# capsens.net
KiCad netlist of a schematic drawn in Altium Designer
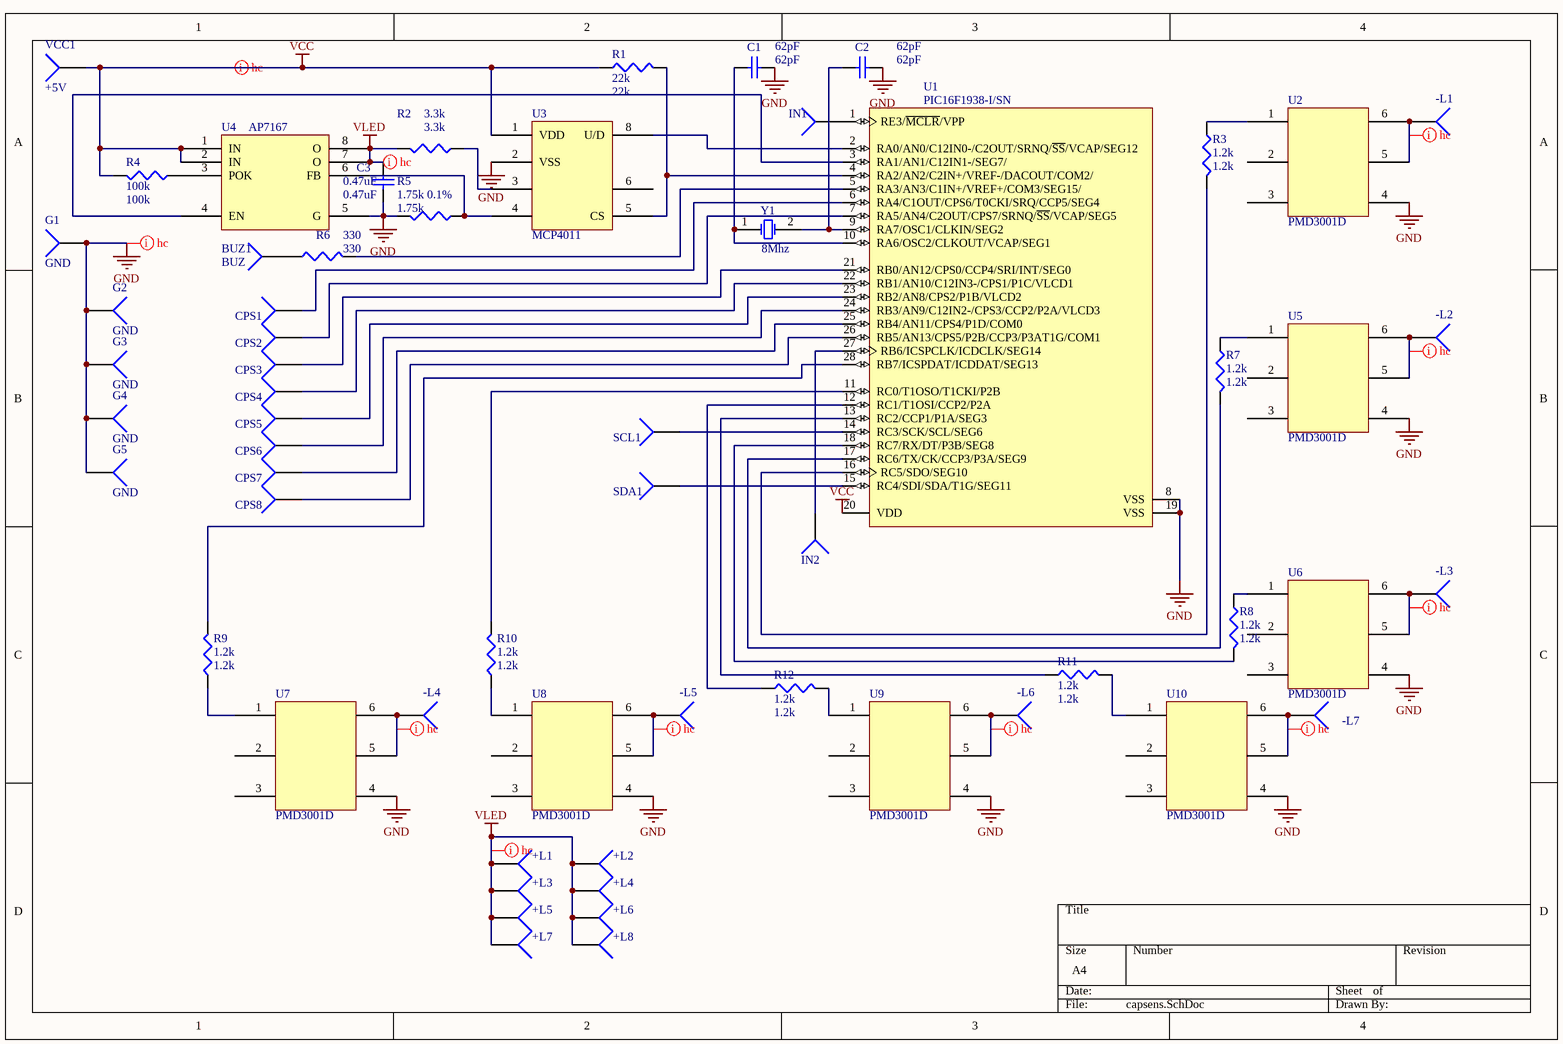
[diagram p0: capsens.SchDoc]

(export (version "E")
  (design (tool "Eeschema 10.0.6"))
  (components
    (comp (ref "+L1")
      (value "+L")
      (footprint "PIN1")
      (description "Socket")
      (fields (field (name "PUBLISHER") "Altium Limited"))
      (libsource (lib "misc") (part "Socket"))
    )
    (comp (ref "+L2")
      (value "+L")
      (footprint "PIN1")
      (description "Socket")
      (fields (field (name "PUBLISHER") "Altium Limited"))
      (libsource (lib "misc") (part "Socket"))
    )
    (comp (ref "+L3")
      (value "+L")
      (footprint "PIN1")
      (description "Socket")
      (fields (field (name "PUBLISHER") "Altium Limited"))
      (libsource (lib "misc") (part "Socket"))
    )
    (comp (ref "+L4")
      (value "+L")
      (footprint "PIN1")
      (description "Socket")
      (fields (field (name "PUBLISHER") "Altium Limited"))
      (libsource (lib "misc") (part "Socket"))
    )
    (comp (ref "+L5")
      (value "+L")
      (footprint "PIN1")
      (description "Socket")
      (fields (field (name "PUBLISHER") "Altium Limited"))
      (libsource (lib "misc") (part "Socket"))
    )
    (comp (ref "+L6")
      (value "+L")
      (footprint "PIN1")
      (description "Socket")
      (fields (field (name "PUBLISHER") "Altium Limited"))
      (libsource (lib "misc") (part "Socket"))
    )
    (comp (ref "+L7")
      (value "+L")
      (footprint "PIN1")
      (description "Socket")
      (fields (field (name "PUBLISHER") "Altium Limited"))
      (libsource (lib "misc") (part "Socket"))
    )
    (comp (ref "+L8")
      (value "+L")
      (footprint "PIN1")
      (description "Socket")
      (fields (field (name "PUBLISHER") "Altium Limited"))
      (libsource (lib "misc") (part "Socket"))
    )
    (comp (ref "-L1")
      (value "-L")
      (footprint "PIN1")
      (description "Socket")
      (fields (field (name "PUBLISHER") "Altium Limited"))
      (libsource (lib "misc") (part "Socket"))
    )
    (comp (ref "-L2")
      (value "-L")
      (footprint "PIN1")
      (description "Socket")
      (fields (field (name "PUBLISHER") "Altium Limited"))
      (libsource (lib "misc") (part "Socket"))
    )
    (comp (ref "-L3")
      (value "-L")
      (footprint "PIN1")
      (description "Socket")
      (fields (field (name "PUBLISHER") "Altium Limited"))
      (libsource (lib "misc") (part "Socket"))
    )
    (comp (ref "-L4")
      (value "-L")
      (footprint "PIN1")
      (description "Socket")
      (fields (field (name "PUBLISHER") "Altium Limited"))
      (libsource (lib "misc") (part "Socket"))
    )
    (comp (ref "-L5")
      (value "-L")
      (footprint "PIN1")
      (description "Socket")
      (fields (field (name "PUBLISHER") "Altium Limited"))
      (libsource (lib "misc") (part "Socket"))
    )
    (comp (ref "-L6")
      (value "-L")
      (footprint "PIN1")
      (description "Socket")
      (fields (field (name "PUBLISHER") "Altium Limited"))
      (libsource (lib "misc") (part "Socket"))
    )
    (comp (ref "-L7")
      (value "-L")
      (footprint "PIN1")
      (description "Socket")
      (fields (field (name "PUBLISHER") "Altium Limited"))
      (libsource (lib "misc") (part "Socket"))
    )
    (comp (ref "BUZ1")
      (value "BUZ")
      (footprint "PIN1")
      (description "Socket")
      (fields (field (name "PUBLISHER") "Altium Limited"))
      (libsource (lib "misc") (part "Socket"))
    )
    (comp (ref "C1")
      (value "62pF")
      (footprint "1608[0603]")
      (description "Capacitor")
      (fields (field (name "ALTIUM_VALUE") "62pF") (field (name "PUBLISHER") "Altium Limited"))
      (libsource (lib "Miscellaneous Devices") (part "Cap"))
    )
    (comp (ref "C2")
      (value "62pF")
      (footprint "1608[0603]")
      (description "Capacitor")
      (fields (field (name "ALTIUM_VALUE") "62pF") (field (name "PUBLISHER") "Altium Limited"))
      (libsource (lib "Miscellaneous Devices") (part "Cap"))
    )
    (comp (ref "C3")
      (value "0.47uF")
      (footprint "1608[0603]")
      (description "Capacitor")
      (fields (field (name "ALTIUM_VALUE") "0.47uF") (field (name "PUBLISHER") "Altium Limited"))
      (libsource (lib "Miscellaneous Devices") (part "Cap"))
    )
    (comp (ref "CPS1")
      (value "CPS")
      (footprint "PIN1L")
      (description "Socket")
      (fields (field (name "PUBLISHER") "Altium Limited"))
      (libsource (lib "misc") (part "Socket"))
    )
    (comp (ref "CPS2")
      (value "CPS")
      (footprint "PIN1L")
      (description "Socket")
      (fields (field (name "PUBLISHER") "Altium Limited"))
      (libsource (lib "misc") (part "Socket"))
    )
    (comp (ref "CPS3")
      (value "CPS")
      (footprint "PIN1L")
      (description "Socket")
      (fields (field (name "PUBLISHER") "Altium Limited"))
      (libsource (lib "misc") (part "Socket"))
    )
    (comp (ref "CPS4")
      (value "CPS")
      (footprint "PIN1L")
      (description "Socket")
      (fields (field (name "PUBLISHER") "Altium Limited"))
      (libsource (lib "misc") (part "Socket"))
    )
    (comp (ref "CPS5")
      (value "CPS")
      (footprint "PIN1L")
      (description "Socket")
      (fields (field (name "PUBLISHER") "Altium Limited"))
      (libsource (lib "misc") (part "Socket"))
    )
    (comp (ref "CPS6")
      (value "CPS")
      (footprint "PIN1L")
      (description "Socket")
      (fields (field (name "PUBLISHER") "Altium Limited"))
      (libsource (lib "misc") (part "Socket"))
    )
    (comp (ref "CPS7")
      (value "CPS")
      (footprint "PIN1L")
      (description "Socket")
      (fields (field (name "PUBLISHER") "Altium Limited"))
      (libsource (lib "misc") (part "Socket"))
    )
    (comp (ref "CPS8")
      (value "CPS")
      (footprint "PIN1L")
      (description "Socket")
      (fields (field (name "PUBLISHER") "Altium Limited"))
      (libsource (lib "misc") (part "Socket"))
    )
    (comp (ref "G1")
      (value "GND")
      (footprint "PIN1")
      (description "Socket")
      (fields (field (name "PUBLISHER") "Altium Limited"))
      (libsource (lib "misc") (part "Socket"))
    )
    (comp (ref "G2")
      (value "GND")
      (footprint "PIN1")
      (description "Socket")
      (fields (field (name "PUBLISHER") "Altium Limited"))
      (libsource (lib "misc") (part "Socket"))
    )
    (comp (ref "G3")
      (value "GND")
      (footprint "PIN1")
      (description "Socket")
      (fields (field (name "PUBLISHER") "Altium Limited"))
      (libsource (lib "misc") (part "Socket"))
    )
    (comp (ref "G4")
      (value "GND")
      (footprint "PIN1")
      (description "Socket")
      (fields (field (name "PUBLISHER") "Altium Limited"))
      (libsource (lib "misc") (part "Socket"))
    )
    (comp (ref "G5")
      (value "GND")
      (footprint "PIN1")
      (description "Socket")
      (fields (field (name "PUBLISHER") "Altium Limited"))
      (libsource (lib "misc") (part "Socket"))
    )
    (comp (ref "IN1")
      (value "IN")
      (footprint "PIN1L")
      (description "Socket")
      (fields (field (name "PUBLISHER") "Altium Limited"))
      (libsource (lib "misc") (part "Socket"))
    )
    (comp (ref "IN2")
      (value "IN")
      (footprint "PIN1L")
      (description "Socket")
      (fields (field (name "PUBLISHER") "Altium Limited"))
      (libsource (lib "misc") (part "Socket"))
    )
    (comp (ref "R1")
      (value "22k")
      (footprint "J1-0603")
      (description "Resistor")
      (fields (field (name "ALTIUM_VALUE") "22k") (field (name "PUBLISHER") "Altium Limited"))
      (libsource (lib "Miscellaneous Devices") (part "Res3"))
    )
    (comp (ref "R2")
      (value "3.3k")
      (footprint "J1-0603")
      (description "Resistor")
      (fields (field (name "ALTIUM_VALUE") "3.3k") (field (name "PUBLISHER") "Altium Limited"))
      (libsource (lib "Miscellaneous Devices") (part "Res3"))
    )
    (comp (ref "R3")
      (value "1.2k")
      (footprint "J1-0603")
      (description "Resistor")
      (fields (field (name "ALTIUM_VALUE") "1.2k") (field (name "PUBLISHER") "Altium Limited"))
      (libsource (lib "Miscellaneous Devices") (part "Res3"))
    )
    (comp (ref "R4")
      (value "100k")
      (footprint "J1-0603")
      (description "Resistor")
      (fields (field (name "ALTIUM_VALUE") "100k") (field (name "PUBLISHER") "Altium Limited"))
      (libsource (lib "Miscellaneous Devices") (part "Res3"))
    )
    (comp (ref "R5")
      (value "1.75k 0.1%")
      (footprint "R1206")
      (description "Resistor")
      (fields (field (name "ALTIUM_VALUE") "1.75k") (field (name "PUBLISHER") "Altium Limited"))
      (libsource (lib "Miscellaneous Devices") (part "Res3"))
    )
    (comp (ref "R6")
      (value "330")
      (footprint "J1-0603")
      (description "Resistor")
      (fields (field (name "ALTIUM_VALUE") "330") (field (name "PUBLISHER") "Altium Limited"))
      (libsource (lib "Miscellaneous Devices") (part "Res3"))
    )
    (comp (ref "R7")
      (value "1.2k")
      (footprint "J1-0603")
      (description "Resistor")
      (fields (field (name "ALTIUM_VALUE") "1.2k") (field (name "PUBLISHER") "Altium Limited"))
      (libsource (lib "Miscellaneous Devices") (part "Res3"))
    )
    (comp (ref "R8")
      (value "1.2k")
      (footprint "J1-0603")
      (description "Resistor")
      (fields (field (name "ALTIUM_VALUE") "1.2k") (field (name "PUBLISHER") "Altium Limited"))
      (libsource (lib "Miscellaneous Devices") (part "Res3"))
    )
    (comp (ref "R9")
      (value "1.2k")
      (footprint "J1-0603")
      (description "Resistor")
      (fields (field (name "ALTIUM_VALUE") "1.2k") (field (name "PUBLISHER") "Altium Limited"))
      (libsource (lib "Miscellaneous Devices") (part "Res3"))
    )
    (comp (ref "R10")
      (value "1.2k")
      (footprint "J1-0603")
      (description "Resistor")
      (fields (field (name "ALTIUM_VALUE") "1.2k") (field (name "PUBLISHER") "Altium Limited"))
      (libsource (lib "Miscellaneous Devices") (part "Res3"))
    )
    (comp (ref "R11")
      (value "1.2k")
      (footprint "J1-0603")
      (description "Resistor")
      (fields (field (name "ALTIUM_VALUE") "1.2k") (field (name "PUBLISHER") "Altium Limited"))
      (libsource (lib "Miscellaneous Devices") (part "Res3"))
    )
    (comp (ref "R12")
      (value "1.2k")
      (footprint "J1-0603")
      (description "Resistor")
      (fields (field (name "ALTIUM_VALUE") "1.2k") (field (name "PUBLISHER") "Altium Limited"))
      (libsource (lib "Miscellaneous Devices") (part "Res3"))
    )
    (comp (ref "SCL1")
      (value "SCL")
      (footprint "PIN1L")
      (description "Socket")
      (fields (field (name "PUBLISHER") "Altium Limited"))
      (libsource (lib "misc") (part "Socket"))
    )
    (comp (ref "SDA1")
      (value "SDA")
      (footprint "PIN1L")
      (description "Socket")
      (fields (field (name "PUBLISHER") "Altium Limited"))
      (libsource (lib "misc") (part "Socket"))
    )
    (comp (ref "U1")
      (value "PIC16F1938-I/SN")
      (footprint "SOIC-SO28_N")
      (fields (field (name "PUBLISHER") "Altium Limited"))
      (libsource (lib "Microchip Microcontroller 8-Bit PIC16") (part "PIC16F1936-I/SO"))
    )
    (comp (ref "U2") (value "PMD3001D") (footprint "SOT457") (libsource (lib "misc") (part "PMD3001D")))
    (comp (ref "U3") (value "MCP4011") (footprint "SOIC150-8_N") (libsource (lib "misc") (part "MCP4011")))
    (comp (ref "U4") (value "AP7167") (footprint "SOIC150-8_N") (libsource (lib "misc") (part "AP7167")))
    (comp (ref "U5") (value "PMD3001D") (footprint "SOT457") (libsource (lib "misc") (part "PMD3001D")))
    (comp (ref "U6") (value "PMD3001D") (footprint "SOT457") (libsource (lib "misc") (part "PMD3001D")))
    (comp (ref "U7") (value "PMD3001D") (footprint "SOT457") (libsource (lib "misc") (part "PMD3001D")))
    (comp (ref "U8") (value "PMD3001D") (footprint "SOT457") (libsource (lib "misc") (part "PMD3001D")))
    (comp (ref "U9") (value "PMD3001D") (footprint "SOT457") (libsource (lib "misc") (part "PMD3001D")))
    (comp (ref "U10") (value "PMD3001D") (footprint "SOT457") (libsource (lib "misc") (part "PMD3001D")))
    (comp (ref "VCC1")
      (value "+5V")
      (footprint "PIN1")
      (description "Socket")
      (fields (field (name "PUBLISHER") "Altium Limited"))
      (libsource (lib "misc") (part "Socket"))
    )
    (comp (ref "Y1")
      (value "8Mhz")
      (footprint "XTAL")
      (description "Crystal Oscillator")
      (fields (field (name "PUBLISHER") "Altium Limited"))
      (libsource (lib "Miscellaneous Devices") (part "XTAL"))
    )
  )
  (nets
    (net (code "1") (name "GND") (class "Default")
      (node (ref "C1") (pin "1") (pinfunction "1_1") (pintype "passive"))
      (node (ref "C2") (pin "1") (pinfunction "1_1") (pintype "passive"))
      (node (ref "C3") (pin "1") (pinfunction "1_1") (pintype "passive"))
      (node (ref "G1") (pin "1") (pinfunction "1_1") (pintype "passive"))
      (node (ref "G2") (pin "1") (pinfunction "1_1") (pintype "passive"))
      (node (ref "G3") (pin "1") (pinfunction "1_1") (pintype "passive"))
      (node (ref "G4") (pin "1") (pinfunction "1_1") (pintype "passive"))
      (node (ref "G5") (pin "1") (pinfunction "1_1") (pintype "passive"))
      (node (ref "R5") (pin "2") (pinfunction "2_2") (pintype "passive"))
      (node (ref "U1") (pin "19") (pinfunction "VSS_19") (pintype "power_in"))
      (node (ref "U1") (pin "8") (pinfunction "VSS_8") (pintype "power_in"))
      (node (ref "U10") (pin "4") (pinfunction "4_4") (pintype "passive"))
      (node (ref "U2") (pin "4") (pinfunction "4_4") (pintype "passive"))
      (node (ref "U3") (pin "2") (pinfunction "VSS_2") (pintype "passive"))
      (node (ref "U4") (pin "5") (pinfunction "G_5") (pintype "passive"))
      (node (ref "U5") (pin "4") (pinfunction "4_4") (pintype "passive"))
      (node (ref "U6") (pin "4") (pinfunction "4_4") (pintype "passive"))
      (node (ref "U7") (pin "4") (pinfunction "4_4") (pintype "passive"))
      (node (ref "U8") (pin "4") (pinfunction "4_4") (pintype "passive"))
      (node (ref "U9") (pin "4") (pinfunction "4_4") (pintype "passive"))
    )
    (net (code "2") (name "Net-(-L1-Pad1)") (class "Default")
      (node (ref "-L1") (pin "1") (pinfunction "1_1") (pintype "passive"))
      (node (ref "U2") (pin "5") (pinfunction "5_5") (pintype "passive"))
      (node (ref "U2") (pin "6") (pinfunction "6_6") (pintype "passive"))
    )
    (net (code "3") (name "Net-(-L2-Pad1)") (class "Default")
      (node (ref "-L2") (pin "1") (pinfunction "1_1") (pintype "passive"))
      (node (ref "U5") (pin "5") (pinfunction "5_5") (pintype "passive"))
      (node (ref "U5") (pin "6") (pinfunction "6_6") (pintype "passive"))
    )
    (net (code "4") (name "Net-(-L3-Pad1)") (class "Default")
      (node (ref "-L3") (pin "1") (pinfunction "1_1") (pintype "passive"))
      (node (ref "U6") (pin "5") (pinfunction "5_5") (pintype "passive"))
      (node (ref "U6") (pin "6") (pinfunction "6_6") (pintype "passive"))
    )
    (net (code "5") (name "Net-(-L4-Pad1)") (class "Default")
      (node (ref "-L4") (pin "1") (pinfunction "1_1") (pintype "passive"))
      (node (ref "U7") (pin "5") (pinfunction "5_5") (pintype "passive"))
      (node (ref "U7") (pin "6") (pinfunction "6_6") (pintype "passive"))
    )
    (net (code "6") (name "Net-(-L5-Pad1)") (class "Default")
      (node (ref "-L5") (pin "1") (pinfunction "1_1") (pintype "passive"))
      (node (ref "U8") (pin "5") (pinfunction "5_5") (pintype "passive"))
      (node (ref "U8") (pin "6") (pinfunction "6_6") (pintype "passive"))
    )
    (net (code "7") (name "Net-(-L6-Pad1)") (class "Default")
      (node (ref "-L6") (pin "1") (pinfunction "1_1") (pintype "passive"))
      (node (ref "U9") (pin "5") (pinfunction "5_5") (pintype "passive"))
      (node (ref "U9") (pin "6") (pinfunction "6_6") (pintype "passive"))
    )
    (net (code "8") (name "Net-(-L7-Pad1)") (class "Default")
      (node (ref "-L7") (pin "1") (pinfunction "1_1") (pintype "passive"))
      (node (ref "U10") (pin "5") (pinfunction "5_5") (pintype "passive"))
      (node (ref "U10") (pin "6") (pinfunction "6_6") (pintype "passive"))
    )
    (net (code "9") (name "Net-(BUZ1-Pad1)") (class "Default")
      (node (ref "BUZ1") (pin "1") (pinfunction "1_1") (pintype "passive"))
      (node (ref "R6") (pin "1") (pinfunction "1_1") (pintype "passive"))
    )
    (net (code "10") (name "Net-(R3-Pad1)") (class "Default")
      (node (ref "R3") (pin "1") (pinfunction "1_1") (pintype "passive"))
      (node (ref "U2") (pin "1") (pinfunction "1_1") (pintype "passive"))
    )
    (net (code "11") (name "Net-(R7-Pad1)") (class "Default")
      (node (ref "R7") (pin "1") (pinfunction "1_1") (pintype "passive"))
      (node (ref "U5") (pin "1") (pinfunction "1_1") (pintype "passive"))
    )
    (net (code "12") (name "Net-(R8-Pad1)") (class "Default")
      (node (ref "R8") (pin "1") (pinfunction "1_1") (pintype "passive"))
      (node (ref "U6") (pin "1") (pinfunction "1_1") (pintype "passive"))
    )
    (net (code "13") (name "Net-(R9-Pad1)") (class "Default")
      (node (ref "R9") (pin "1") (pinfunction "1_1") (pintype "passive"))
      (node (ref "U7") (pin "1") (pinfunction "1_1") (pintype "passive"))
    )
    (net (code "14") (name "Net-(R10-Pad1)") (class "Default")
      (node (ref "R10") (pin "1") (pinfunction "1_1") (pintype "passive"))
      (node (ref "U8") (pin "1") (pinfunction "1_1") (pintype "passive"))
    )
    (net (code "15") (name "Net-(R11-Pad2)") (class "Default")
      (node (ref "R11") (pin "2") (pinfunction "2_2") (pintype "passive"))
      (node (ref "U10") (pin "1") (pinfunction "1_1") (pintype "passive"))
    )
    (net (code "16") (name "Net-(R12-Pad2)") (class "Default")
      (node (ref "R12") (pin "2") (pinfunction "2_2") (pintype "passive"))
      (node (ref "U9") (pin "1") (pinfunction "1_1") (pintype "passive"))
    )
    (net (code "17") (name "Net-(U1-RA0{slash}AN0{slash}C12IN0-{slash}C2OUT{slash}SRNQ{slash}~{SS}{slash}VCAP{slash}SEG12)") (class "Default")
      (node (ref "U1") (pin "2") (pinfunction "RA0/AN0/C12IN0-/C2OUT/SRNQ/~{SS}/VCAP/SEG12_2") (pintype "bidirectional"))
      (node (ref "U3") (pin "8") (pinfunction "U/D_8") (pintype "passive"))
    )
    (net (code "18") (name "Net-(U1-RA1{slash}AN1{slash}C12IN1-{slash}SEG7{slash})") (class "Default")
      (node (ref "U1") (pin "3") (pinfunction "RA1/AN1/C12IN1-/SEG7/_3") (pintype "bidirectional"))
      (node (ref "U4") (pin "4") (pinfunction "EN_4") (pintype "passive"))
    )
    (net (code "19") (name "Net-(U1-RA2{slash}AN2{slash}C2IN+{slash}VREF-{slash}DACOUT{slash}COM2{slash})") (class "Default")
      (node (ref "R1") (pin "2") (pinfunction "2_2") (pintype "passive"))
      (node (ref "U1") (pin "4") (pinfunction "RA2/AN2/C2IN+/VREF-/DACOUT/COM2/_4") (pintype "bidirectional"))
      (node (ref "U3") (pin "5") (pinfunction "CS_5") (pintype "passive"))
    )
    (net (code "20") (name "Net-(U1-RA3{slash}AN3{slash}C1IN+{slash}VREF+{slash}COM3{slash}SEG15{slash})") (class "Default")
      (node (ref "R6") (pin "2") (pinfunction "2_2") (pintype "passive"))
      (node (ref "U1") (pin "5") (pinfunction "RA3/AN3/C1IN+/VREF+/COM3/SEG15/_5") (pintype "bidirectional"))
    )
    (net (code "21") (name "Net-(U1-RA4{slash}C1OUT{slash}CPS6{slash}T0CKI{slash}SRQ{slash}CCP5{slash}SEG4)") (class "Default")
      (node (ref "CPS1") (pin "1") (pinfunction "1_1") (pintype "passive"))
      (node (ref "U1") (pin "6") (pinfunction "RA4/C1OUT/CPS6/T0CKI/SRQ/CCP5/SEG4_6") (pintype "bidirectional"))
    )
    (net (code "22") (name "Net-(U1-RA5{slash}AN4{slash}C2OUT{slash}CPS7{slash}SRNQ{slash}~{SS}{slash}VCAP{slash}SEG5)") (class "Default")
      (node (ref "CPS2") (pin "1") (pinfunction "1_1") (pintype "passive"))
      (node (ref "U1") (pin "7") (pinfunction "RA5/AN4/C2OUT/CPS7/SRNQ/~{SS}/VCAP/SEG5_7") (pintype "bidirectional"))
    )
    (net (code "23") (name "Net-(U1-RA6{slash}OSC2{slash}CLKOUT{slash}VCAP{slash}SEG1)") (class "Default")
      (node (ref "C1") (pin "2") (pinfunction "2_2") (pintype "passive"))
      (node (ref "U1") (pin "10") (pinfunction "RA6/OSC2/CLKOUT/VCAP/SEG1_10") (pintype "bidirectional"))
      (node (ref "Y1") (pin "1") (pinfunction "OSC1_1") (pintype "passive"))
    )
    (net (code "24") (name "Net-(U1-RA7{slash}OSC1{slash}CLKIN{slash}SEG2)") (class "Default")
      (node (ref "C2") (pin "2") (pinfunction "2_2") (pintype "passive"))
      (node (ref "U1") (pin "9") (pinfunction "RA7/OSC1/CLKIN/SEG2_9") (pintype "bidirectional"))
      (node (ref "Y1") (pin "2") (pinfunction "OSC2_2") (pintype "passive"))
    )
    (net (code "25") (name "Net-(U1-RB0{slash}AN12{slash}CPS0{slash}CCP4{slash}SRI{slash}INT{slash}SEG0)") (class "Default")
      (node (ref "CPS3") (pin "1") (pinfunction "1_1") (pintype "passive"))
      (node (ref "U1") (pin "21") (pinfunction "RB0/AN12/CPS0/CCP4/SRI/INT/SEG0_21") (pintype "bidirectional"))
    )
    (net (code "26") (name "Net-(U1-RB1{slash}AN10{slash}C12IN3-{slash}CPS1{slash}P1C{slash}VLCD1)") (class "Default")
      (node (ref "CPS4") (pin "1") (pinfunction "1_1") (pintype "passive"))
      (node (ref "U1") (pin "22") (pinfunction "RB1/AN10/C12IN3-/CPS1/P1C/VLCD1_22") (pintype "bidirectional"))
    )
    (net (code "27") (name "Net-(U1-RB2{slash}AN8{slash}CPS2{slash}P1B{slash}VLCD2)") (class "Default")
      (node (ref "CPS5") (pin "1") (pinfunction "1_1") (pintype "passive"))
      (node (ref "U1") (pin "23") (pinfunction "RB2/AN8/CPS2/P1B/VLCD2_23") (pintype "bidirectional"))
    )
    (net (code "28") (name "Net-(U1-RB3{slash}AN9{slash}C12IN2-{slash}CPS3{slash}CCP2{slash}P2A{slash}VLCD3)") (class "Default")
      (node (ref "CPS6") (pin "1") (pinfunction "1_1") (pintype "passive"))
      (node (ref "U1") (pin "24") (pinfunction "RB3/AN9/C12IN2-/CPS3/CCP2/P2A/VLCD3_24") (pintype "bidirectional"))
    )
    (net (code "29") (name "Net-(U1-RB4{slash}AN11{slash}CPS4{slash}P1D{slash}COM0)") (class "Default")
      (node (ref "CPS7") (pin "1") (pinfunction "1_1") (pintype "passive"))
      (node (ref "U1") (pin "25") (pinfunction "RB4/AN11/CPS4/P1D/COM0_25") (pintype "bidirectional"))
    )
    (net (code "30") (name "Net-(U1-RB5{slash}AN13{slash}CPS5{slash}P2B{slash}CCP3{slash}P3AT1G{slash}COM1)") (class "Default")
      (node (ref "CPS8") (pin "1") (pinfunction "1_1") (pintype "passive"))
      (node (ref "U1") (pin "26") (pinfunction "RB5/AN13/CPS5/P2B/CCP3/P3AT1G/COM1_26") (pintype "bidirectional"))
    )
    (net (code "31") (name "Net-(U1-RB6{slash}ICSPCLK{slash}ICDCLK{slash}SEG14)") (class "Default")
      (node (ref "IN2") (pin "1") (pinfunction "1_1") (pintype "passive"))
      (node (ref "U1") (pin "27") (pinfunction "RB6/ICSPCLK/ICDCLK/SEG14_27") (pintype "bidirectional"))
    )
    (net (code "32") (name "Net-(U1-RB7{slash}ICSPDAT{slash}ICDDAT{slash}SEG13)") (class "Default")
      (node (ref "R9") (pin "2") (pinfunction "2_2") (pintype "passive"))
      (node (ref "U1") (pin "28") (pinfunction "RB7/ICSPDAT/ICDDAT/SEG13_28") (pintype "bidirectional"))
    )
    (net (code "33") (name "Net-(U1-RC0{slash}T1OSO{slash}T1CKI{slash}P2B)") (class "Default")
      (node (ref "R10") (pin "2") (pinfunction "2_2") (pintype "passive"))
      (node (ref "U1") (pin "11") (pinfunction "RC0/T1OSO/T1CKI/P2B_11") (pintype "bidirectional"))
    )
    (net (code "34") (name "Net-(U1-RC1{slash}T1OSI{slash}CCP2{slash}P2A)") (class "Default")
      (node (ref "R12") (pin "1") (pinfunction "1_1") (pintype "passive"))
      (node (ref "U1") (pin "12") (pinfunction "RC1/T1OSI/CCP2/P2A_12") (pintype "bidirectional"))
    )
    (net (code "35") (name "Net-(U1-RC2{slash}CCP1{slash}P1A{slash}SEG3)") (class "Default")
      (node (ref "R11") (pin "1") (pinfunction "1_1") (pintype "passive"))
      (node (ref "U1") (pin "13") (pinfunction "RC2/CCP1/P1A/SEG3_13") (pintype "bidirectional"))
    )
    (net (code "36") (name "Net-(U1-RC3{slash}SCK{slash}SCL{slash}SEG6)") (class "Default")
      (node (ref "SCL1") (pin "1") (pinfunction "1_1") (pintype "passive"))
      (node (ref "U1") (pin "14") (pinfunction "RC3/SCK/SCL/SEG6_14") (pintype "bidirectional"))
    )
    (net (code "37") (name "Net-(U1-RC4{slash}SDI{slash}SDA{slash}T1G{slash}SEG11)") (class "Default")
      (node (ref "SDA1") (pin "1") (pinfunction "1_1") (pintype "passive"))
      (node (ref "U1") (pin "15") (pinfunction "RC4/SDI/SDA/T1G/SEG11_15") (pintype "bidirectional"))
    )
    (net (code "38") (name "Net-(U1-RC5{slash}SDO{slash}SEG10)") (class "Default")
      (node (ref "R3") (pin "2") (pinfunction "2_2") (pintype "passive"))
      (node (ref "U1") (pin "16") (pinfunction "RC5/SDO/SEG10_16") (pintype "bidirectional"))
    )
    (net (code "39") (name "Net-(U1-RC6{slash}TX{slash}CK{slash}CCP3{slash}P3A{slash}SEG9)") (class "Default")
      (node (ref "R7") (pin "2") (pinfunction "2_2") (pintype "passive"))
      (node (ref "U1") (pin "17") (pinfunction "RC6/TX/CK/CCP3/P3A/SEG9_17") (pintype "bidirectional"))
    )
    (net (code "40") (name "Net-(U1-RC7{slash}RX{slash}DT{slash}P3B{slash}SEG8)") (class "Default")
      (node (ref "R8") (pin "2") (pinfunction "2_2") (pintype "passive"))
      (node (ref "U1") (pin "18") (pinfunction "RC7/RX/DT/P3B/SEG8_18") (pintype "bidirectional"))
    )
    (net (code "41") (name "Net-(U1-RE3{slash}~{MCLR}{slash}VPP)") (class "Default")
      (node (ref "IN1") (pin "1") (pinfunction "1_1") (pintype "passive"))
      (node (ref "U1") (pin "1") (pinfunction "RE3/~{MCLR}/VPP_1") (pintype "bidirectional"))
    )
    (net (code "42") (name "Net-(U3-A)") (class "Default")
      (node (ref "R2") (pin "1") (pinfunction "1_1") (pintype "passive"))
      (node (ref "U3") (pin "3") (pinfunction "A_3") (pintype "passive"))
    )
    (net (code "43") (name "Net-(U3-W)") (class "Default")
      (node (ref "R5") (pin "1") (pinfunction "1_1") (pintype "passive"))
      (node (ref "U3") (pin "4") (pinfunction "W_4") (pintype "passive"))
      (node (ref "U4") (pin "6") (pinfunction "FB_6") (pintype "passive"))
    )
    (net (code "44") (name "Net-(U4-POK)") (class "Default")
      (node (ref "R4") (pin "1") (pinfunction "1_1") (pintype "passive"))
      (node (ref "U4") (pin "3") (pinfunction "POK_3") (pintype "passive"))
    )
    (net (code "45") (name "VCC") (class "Default")
      (node (ref "R1") (pin "1") (pinfunction "1_1") (pintype "passive"))
      (node (ref "R4") (pin "2") (pinfunction "2_2") (pintype "passive"))
      (node (ref "U1") (pin "20") (pinfunction "VDD_20") (pintype "power_in"))
      (node (ref "U3") (pin "1") (pinfunction "VDD_1") (pintype "passive"))
      (node (ref "U4") (pin "1") (pinfunction "IN_1") (pintype "passive"))
      (node (ref "U4") (pin "2") (pinfunction "IN_2") (pintype "passive"))
      (node (ref "VCC1") (pin "1") (pinfunction "1_1") (pintype "passive"))
    )
    (net (code "46") (name "VLED") (class "Default")
      (node (ref "+L1") (pin "1") (pinfunction "1_1") (pintype "passive"))
      (node (ref "+L2") (pin "1") (pinfunction "1_1") (pintype "passive"))
      (node (ref "+L3") (pin "1") (pinfunction "1_1") (pintype "passive"))
      (node (ref "+L4") (pin "1") (pinfunction "1_1") (pintype "passive"))
      (node (ref "+L5") (pin "1") (pinfunction "1_1") (pintype "passive"))
      (node (ref "+L6") (pin "1") (pinfunction "1_1") (pintype "passive"))
      (node (ref "+L7") (pin "1") (pinfunction "1_1") (pintype "passive"))
      (node (ref "+L8") (pin "1") (pinfunction "1_1") (pintype "passive"))
      (node (ref "C3") (pin "2") (pinfunction "2_2") (pintype "passive"))
      (node (ref "R2") (pin "2") (pinfunction "2_2") (pintype "passive"))
      (node (ref "U4") (pin "7") (pinfunction "O_7") (pintype "passive"))
      (node (ref "U4") (pin "8") (pinfunction "O_8") (pintype "passive"))
    )
    (net (code "47") (name "unconnected-(U2-Pad2)") (class "Default")
      (node (ref "U2") (pin "2") (pinfunction "2_2") (pintype "passive"))
    )
    (net (code "48") (name "unconnected-(U2-Pad3)") (class "Default")
      (node (ref "U2") (pin "3") (pinfunction "3_3") (pintype "passive"))
    )
    (net (code "49") (name "unconnected-(U3-B-Pad6)") (class "Default")
      (node (ref "U3") (pin "6") (pinfunction "B_6") (pintype "passive"))
    )
    (net (code "50") (name "unconnected-(U5-Pad2)") (class "Default")
      (node (ref "U5") (pin "2") (pinfunction "2_2") (pintype "passive"))
    )
    (net (code "51") (name "unconnected-(U5-Pad3)") (class "Default")
      (node (ref "U5") (pin "3") (pinfunction "3_3") (pintype "passive"))
    )
    (net (code "52") (name "unconnected-(U6-Pad2)") (class "Default")
      (node (ref "U6") (pin "2") (pinfunction "2_2") (pintype "passive"))
    )
    (net (code "53") (name "unconnected-(U6-Pad3)") (class "Default")
      (node (ref "U6") (pin "3") (pinfunction "3_3") (pintype "passive"))
    )
    (net (code "54") (name "unconnected-(U7-Pad2)") (class "Default")
      (node (ref "U7") (pin "2") (pinfunction "2_2") (pintype "passive"))
    )
    (net (code "55") (name "unconnected-(U7-Pad3)") (class "Default")
      (node (ref "U7") (pin "3") (pinfunction "3_3") (pintype "passive"))
    )
    (net (code "56") (name "unconnected-(U8-Pad2)") (class "Default")
      (node (ref "U8") (pin "2") (pinfunction "2_2") (pintype "passive"))
    )
    (net (code "57") (name "unconnected-(U8-Pad3)") (class "Default")
      (node (ref "U8") (pin "3") (pinfunction "3_3") (pintype "passive"))
    )
    (net (code "58") (name "unconnected-(U9-Pad2)") (class "Default")
      (node (ref "U9") (pin "2") (pinfunction "2_2") (pintype "passive"))
    )
    (net (code "59") (name "unconnected-(U9-Pad3)") (class "Default")
      (node (ref "U9") (pin "3") (pinfunction "3_3") (pintype "passive"))
    )
    (net (code "60") (name "unconnected-(U10-Pad2)") (class "Default")
      (node (ref "U10") (pin "2") (pinfunction "2_2") (pintype "passive"))
    )
    (net (code "61") (name "unconnected-(U10-Pad3)") (class "Default")
      (node (ref "U10") (pin "3") (pinfunction "3_3") (pintype "passive"))
    )
  )
)
